# TBD_Sensor.net
KiCad netlist of a schematic drawn in Altium Designer
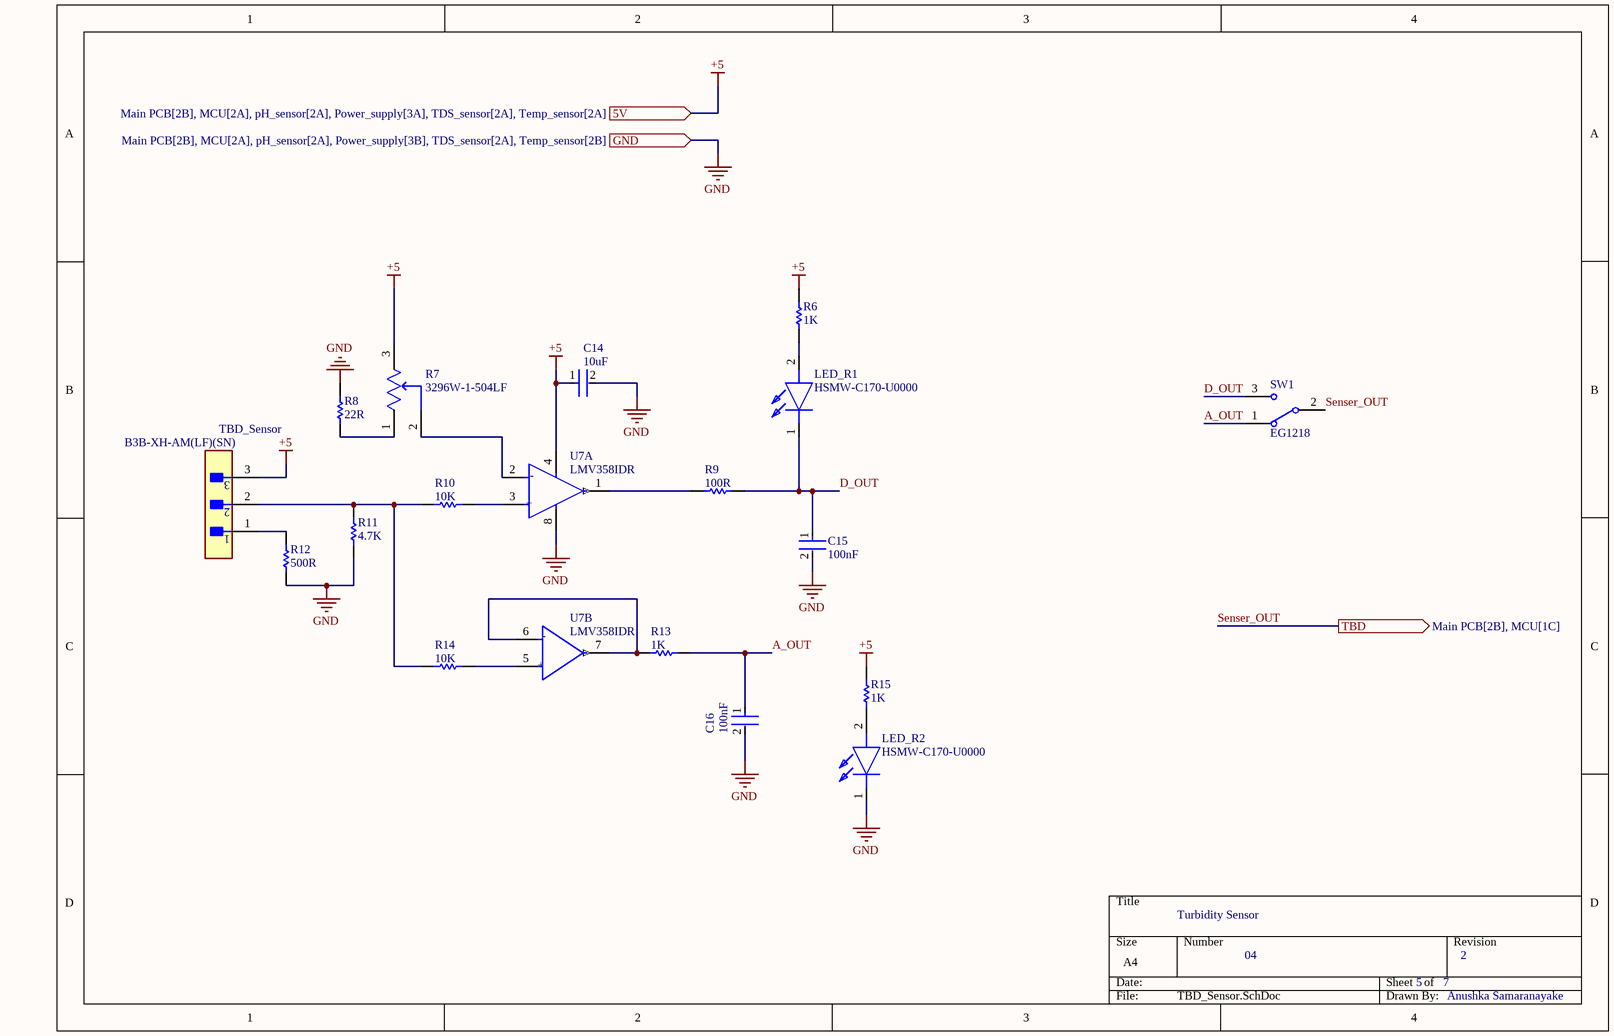
[diagram p0: TBD_Sensor.SchDoc]

(export (version "E")
  (design (tool "Eeschema 10.0.6"))
  (components
    (comp (ref "C14")
      (value "10uF")
      (footprint "FP-CL31-IPC_B")
      (description "Cap Ceramic 100nF 50V X7R ±10% SMD 1206 +125°C Embossed T/R")
      (fields (field (name "VOLTAGE") "50V") (field (name "TOLERANCE") "10%"))
      (libsource (lib "Altium Content Vault") (part "b4654b650e69147ec39a6b967a45e02"))
    )
    (comp (ref "C15")
      (value "100nF")
      (footprint "FP-CL31-IPC_B")
      (description "Cap Ceramic 100nF 50V X7R ±10% SMD 1206 +125°C Embossed T/R")
      (fields (field (name "VOLTAGE") "50V") (field (name "TOLERANCE") "10%"))
      (libsource (lib "Altium Content Vault") (part "b4654b650e69147ec39a6b967a45e02"))
    )
    (comp (ref "C16")
      (value "100nF")
      (footprint "FP-CL31-IPC_B")
      (description "Cap Ceramic 100nF 50V X7R ±10% SMD 1206 +125°C Embossed T/R")
      (fields (field (name "VOLTAGE") "50V") (field (name "TOLERANCE") "10%"))
      (libsource (lib "Altium Content Vault") (part "b4654b650e69147ec39a6b967a45e02"))
    )
    (comp (ref "LED_R1")
      (value "HSMW-C170-U0000")
      (footprint "SamacSys:LEDC2012X90N")
      (description "LED")
      (fields (field (name "MOUSER PART NUMBER") "630-HSMW-C170-U0000"))
      (libsource (lib "*") (part "HSMW-C170-U0000"))
    )
    (comp (ref "LED_R2")
      (value "HSMW-C170-U0000")
      (footprint "SamacSys:LEDC2012X90N")
      (description "LED")
      (fields (field (name "MOUSER PART NUMBER") "630-HSMW-C170-U0000"))
      (libsource (lib "*") (part "HSMW-C170-U0000"))
    )
    (comp (ref "R6")
      (value "1K")
      (footprint "RESC3216X70X50LL20T25")
      (fields (field (name "MANUFACTURER") "Panasonic") (field (name "PART NUMBER") "ERA8AEB103V"))
      (libsource (lib "Altium Content Vault") (part "RES"))
    )
    (comp (ref "R7")
      (value "3296W-1-504LF")
      (footprint "FP-3296W-MFG")
      (description "TRIMMER 500K OHM 0.5W PC PIN TOP")
      (fields
        (field (name "MANUFACTURER") "Bourns")
        (field (name "OCTOPART") "https://octopart.com/3296w-1-504lf-bourns-143884")
      )
      (libsource (lib "Altium Content Vault") (part "8d460c8a6f7ec10b1759d1b9c49aa93"))
    )
    (comp (ref "R8")
      (value "22R")
      (footprint "RESC2013X60X35ML10T20")
      (description "Chip Resistor, 1 KOhm, +/- 1%, 125 mW, -55 to 155 degC, 0805 (2012 Metric), RoHS, Tape and Reel")
      (fields (field (name "TOLERANCE") "1%") (field (name "MANUFACTURER") "Yageo"))
      (libsource (lib "Altium Content Vault") (part "RES-2"))
    )
    (comp (ref "R9")
      (value "100R")
      (footprint "RESC2013X60X35ML10T20")
      (description "Chip Resistor, 1 KOhm, +/- 1%, 125 mW, -55 to 155 degC, 0805 (2012 Metric), RoHS, Tape and Reel")
      (fields (field (name "TOLERANCE") "1%") (field (name "MANUFACTURER") "Yageo"))
      (libsource (lib "Altium Content Vault") (part "RES-2"))
    )
    (comp (ref "R10")
      (value "10K")
      (footprint "RESC3216X70X50LL20T25")
      (fields (field (name "MANUFACTURER") "Panasonic") (field (name "PART NUMBER") "ERA8AEB103V"))
      (libsource (lib "Altium Content Vault") (part "RES"))
    )
    (comp (ref "R11")
      (value "4.7K")
      (footprint "RESC3216X70X50LL20T25")
      (fields (field (name "MANUFACTURER") "Panasonic") (field (name "PART NUMBER") "ERA8AEB103V"))
      (libsource (lib "Altium Content Vault") (part "RES"))
    )
    (comp (ref "R12")
      (value "500R")
      (footprint "RESC2013X60X35ML10T20")
      (description "Chip Resistor, 1 KOhm, +/- 1%, 125 mW, -55 to 155 degC, 0805 (2012 Metric), RoHS, Tape and Reel")
      (fields (field (name "TOLERANCE") "1%") (field (name "MANUFACTURER") "Yageo"))
      (libsource (lib "Altium Content Vault") (part "RES-2"))
    )
    (comp (ref "R13")
      (value "1K")
      (footprint "RESC3216X70X50LL20T25")
      (fields (field (name "MANUFACTURER") "Panasonic") (field (name "PART NUMBER") "ERA8AEB103V"))
      (libsource (lib "Altium Content Vault") (part "RES"))
    )
    (comp (ref "R14")
      (value "10K")
      (footprint "RESC3216X70X50LL20T25")
      (fields (field (name "MANUFACTURER") "Panasonic") (field (name "PART NUMBER") "ERA8AEB103V"))
      (libsource (lib "Altium Content Vault") (part "RES"))
    )
    (comp (ref "R15")
      (value "1K")
      (footprint "RESC3216X70X50LL20T25")
      (fields (field (name "MANUFACTURER") "Panasonic") (field (name "PART NUMBER") "ERA8AEB103V"))
      (libsource (lib "Altium Content Vault") (part "RES"))
    )
    (comp (ref "SW1")
      (value "EG1218")
      (footprint "ESWI-EG1218_V")
      (description "Slide Switch, 500 V, -20 to 70 degC, 3-Pin THD, RoHS")
      (libsource (lib "Altium Content Vault") (part "SW-SPDT-3_B"))
    )
    (comp (ref "TBD_Sensor")
      (value "B3B-XH-AM(LF)(SN)")
      (footprint "FP-B3B-XH-AM_LF_SN-MFG")
      (description "CONN HEADER VERT 3POS 2.5MM")
      (libsource (lib "Altium Content Vault") (part "0d3f023dd272f625e17a2be33dea85f"))
    )
    (comp (ref "U7")
      (value "LMV358IDR")
      (footprint "FP-D0008A-MFG")
      (description "IC OPAMP GP 2 CIRCUIT 8SOIC")
      (libsource (lib "Altium Content Vault") (part "1f85fec4e6914445158f776dbf16c1d"))
    )
  )
  (nets
    (net (code "1") (name "+5") (class "Default")
      (node (ref "C14") (pin "1") (pinfunction "1_1") (pintype "passive"))
      (node (ref "R15") (pin "1") (pinfunction "1_1") (pintype "passive"))
      (node (ref "R6") (pin "1") (pinfunction "1_1") (pintype "passive"))
      (node (ref "R7") (pin "3") (pinfunction "CW_3") (pintype "passive"))
      (node (ref "TBD_Sensor") (pin "3") (pinfunction "3_3") (pintype "passive"))
      (node (ref "U7") (pin "4") (pinfunction "GND_4") (pintype "passive"))
    )
    (net (code "2") (name "/A_OUT") (class "Default")
      (node (ref "C16") (pin "1") (pinfunction "1_1") (pintype "passive"))
      (node (ref "R13") (pin "1") (pinfunction "1_1") (pintype "passive"))
      (node (ref "SW1") (pin "1") (pinfunction "1_1") (pintype "passive"))
    )
    (net (code "3") (name "/D_OUT") (class "Default")
      (node (ref "C15") (pin "1") (pinfunction "1_1") (pintype "passive"))
      (node (ref "LED_R1") (pin "1") (pinfunction "K_1") (pintype "passive"))
      (node (ref "R9") (pin "2") (pinfunction "2_2") (pintype "passive"))
      (node (ref "SW1") (pin "3") (pinfunction "3_3") (pintype "passive"))
    )
    (net (code "4") (name "/Senser_OUT") (class "Default")
      (node (ref "SW1") (pin "2") (pinfunction "COM_2") (pintype "passive"))
    )
    (net (code "5") (name "GND") (class "Default")
      (node (ref "C14") (pin "2") (pinfunction "2_2") (pintype "passive"))
      (node (ref "C15") (pin "2") (pinfunction "2_2") (pintype "passive"))
      (node (ref "C16") (pin "2") (pinfunction "2_2") (pintype "passive"))
      (node (ref "LED_R2") (pin "1") (pinfunction "K_1") (pintype "passive"))
      (node (ref "R11") (pin "2") (pinfunction "2_2") (pintype "passive"))
      (node (ref "R12") (pin "1") (pinfunction "1_1") (pintype "passive"))
      (node (ref "R8") (pin "2") (pinfunction "2_2") (pintype "passive"))
      (node (ref "U7") (pin "8") (pinfunction "VCC+_8") (pintype "passive"))
    )
    (net (code "6") (name "Net-(LED_R1-A)") (class "Default")
      (node (ref "LED_R1") (pin "2") (pinfunction "A_2") (pintype "passive"))
      (node (ref "R6") (pin "2") (pinfunction "2_2") (pintype "passive"))
    )
    (net (code "7") (name "Net-(LED_R2-A)") (class "Default")
      (node (ref "LED_R2") (pin "2") (pinfunction "A_2") (pintype "passive"))
      (node (ref "R15") (pin "2") (pinfunction "2_2") (pintype "passive"))
    )
    (net (code "8") (name "Net-(R7-CCW)") (class "Default")
      (node (ref "R7") (pin "1") (pinfunction "CCW_1") (pintype "passive"))
      (node (ref "R8") (pin "1") (pinfunction "1_1") (pintype "passive"))
    )
    (net (code "9") (name "Net-(R7-WIPER)") (class "Default")
      (node (ref "R7") (pin "2") (pinfunction "WIPER_2") (pintype "passive"))
      (node (ref "U7") (pin "2") (pinfunction "1IN-_2") (pintype "tri_state"))
    )
    (net (code "10") (name "Net-(R10-Pad2)") (class "Default")
      (node (ref "R10") (pin "2") (pinfunction "2_2") (pintype "passive"))
      (node (ref "R11") (pin "1") (pinfunction "1_1") (pintype "passive"))
      (node (ref "R14") (pin "2") (pinfunction "2_2") (pintype "passive"))
      (node (ref "TBD_Sensor") (pin "2") (pinfunction "2_2") (pintype "passive"))
    )
    (net (code "11") (name "Net-(R12-Pad2)") (class "Default")
      (node (ref "R12") (pin "2") (pinfunction "2_2") (pintype "passive"))
      (node (ref "TBD_Sensor") (pin "1") (pinfunction "1_1") (pintype "passive"))
    )
    (net (code "12") (name "Net-(U7A-1IN+)") (class "Default")
      (node (ref "R10") (pin "1") (pinfunction "1_1") (pintype "passive"))
      (node (ref "U7") (pin "3") (pinfunction "1IN+_3") (pintype "tri_state"))
    )
    (net (code "13") (name "Net-(U7A-OUT)") (class "Default")
      (node (ref "R9") (pin "1") (pinfunction "1_1") (pintype "passive"))
      (node (ref "U7") (pin "1") (pinfunction "OUT_1") (pintype "output"))
    )
    (net (code "14") (name "Net-(U7B-2IN+)") (class "Default")
      (node (ref "R14") (pin "1") (pinfunction "1_1") (pintype "passive"))
      (node (ref "U7") (pin "5") (pinfunction "2IN+_5") (pintype "tri_state"))
    )
    (net (code "15") (name "Net-(U7B-2IN-)") (class "Default")
      (node (ref "R13") (pin "2") (pinfunction "2_2") (pintype "passive"))
      (node (ref "U7") (pin "6") (pinfunction "2IN-_6") (pintype "tri_state"))
      (node (ref "U7") (pin "7") (pinfunction "2OUT_7") (pintype "output"))
    )
  )
)
